# PWM.net
KiCad netlist of a schematic drawn in Altium Designer
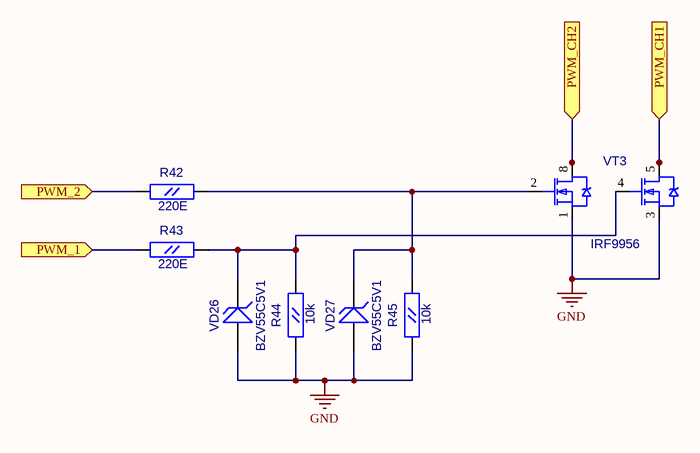
[diagram p0: PWM.SchDoc]

(export (version "E")
  (design (tool "Eeschema 10.0.6"))
  (components
    (comp (ref "R42")
      (value "220E")
      (footprint "RC0603")
      (description "RC0603")
      (libsource (lib "gprs_modem_2") (part "RC0603"))
    )
    (comp (ref "R43")
      (value "220E")
      (footprint "RC0603")
      (description "RC0603")
      (libsource (lib "gprs_modem_2") (part "RC0603"))
    )
    (comp (ref "R44")
      (value "10k")
      (footprint "RC0603")
      (description "RC0603")
      (libsource (lib "gprs_modem_2") (part "RC0603"))
    )
    (comp (ref "R45")
      (value "10k")
      (footprint "RC0603")
      (description "RC0603")
      (libsource (lib "gprs_modem_2") (part "RC0603"))
    )
    (comp (ref "VD26")
      (value "BZV55C5V1")
      (footprint "SOD-80")
      (description "Zener Voltage Regulator Diode")
      (libsource (lib "gprs_modem_2") (part "BZV55C5V1"))
    )
    (comp (ref "VD27")
      (value "BZV55C5V1")
      (footprint "SOD-80")
      (description "Zener Voltage Regulator Diode")
      (libsource (lib "gprs_modem_2") (part "BZV55C5V1"))
    )
    (comp (ref "VT3")
      (value "IRF9956")
      (footprint "SO-8")
      (description "HEXFET Power MOSFET")
      (libsource (lib "gprs_modem_2") (part "IRF9956"))
    )
  )
  (nets
    (net (code "1") (name "/PWM_1") (class "Default")
      (node (ref "R43") (pin "1") (pinfunction "A_1") (pintype "passive"))
    )
    (net (code "2") (name "/PWM_2") (class "Default")
      (node (ref "R42") (pin "1") (pinfunction "A_1") (pintype "passive"))
    )
    (net (code "3") (name "/PWM_CH1") (class "Default")
      (node (ref "VT3") (pin "5") (pinfunction "D_5") (pintype "passive"))
      (node (ref "VT3") (pin "6") (pinfunction "D_6") (pintype "passive"))
    )
    (net (code "4") (name "/PWM_CH2") (class "Default")
      (node (ref "VT3") (pin "7") (pinfunction "D_7") (pintype "passive"))
      (node (ref "VT3") (pin "8") (pinfunction "D_8") (pintype "passive"))
    )
    (net (code "5") (name "GND") (class "Default")
      (node (ref "R44") (pin "1") (pinfunction "A_1") (pintype "passive"))
      (node (ref "R45") (pin "1") (pinfunction "A_1") (pintype "passive"))
      (node (ref "VD26") (pin "1") (pinfunction "A_1") (pintype "passive"))
      (node (ref "VD27") (pin "1") (pinfunction "A_1") (pintype "passive"))
      (node (ref "VT3") (pin "1") (pinfunction "S_1") (pintype "passive"))
      (node (ref "VT3") (pin "3") (pinfunction "S_3") (pintype "passive"))
    )
    (net (code "6") (name "Net-(R42-B)") (class "Default")
      (node (ref "R42") (pin "2") (pinfunction "B_2") (pintype "passive"))
      (node (ref "R45") (pin "2") (pinfunction "B_2") (pintype "passive"))
      (node (ref "VD27") (pin "2") (pintype "passive"))
      (node (ref "VT3") (pin "2") (pinfunction "G_2") (pintype "passive"))
    )
    (net (code "7") (name "Net-(R43-B)") (class "Default")
      (node (ref "R43") (pin "2") (pinfunction "B_2") (pintype "passive"))
      (node (ref "R44") (pin "2") (pinfunction "B_2") (pintype "passive"))
      (node (ref "VD26") (pin "2") (pintype "passive"))
      (node (ref "VT3") (pin "4") (pinfunction "G_4") (pintype "passive"))
    )
  )
)
